# H09R9.net
KiCad netlist of a schematic drawn in EAGLE
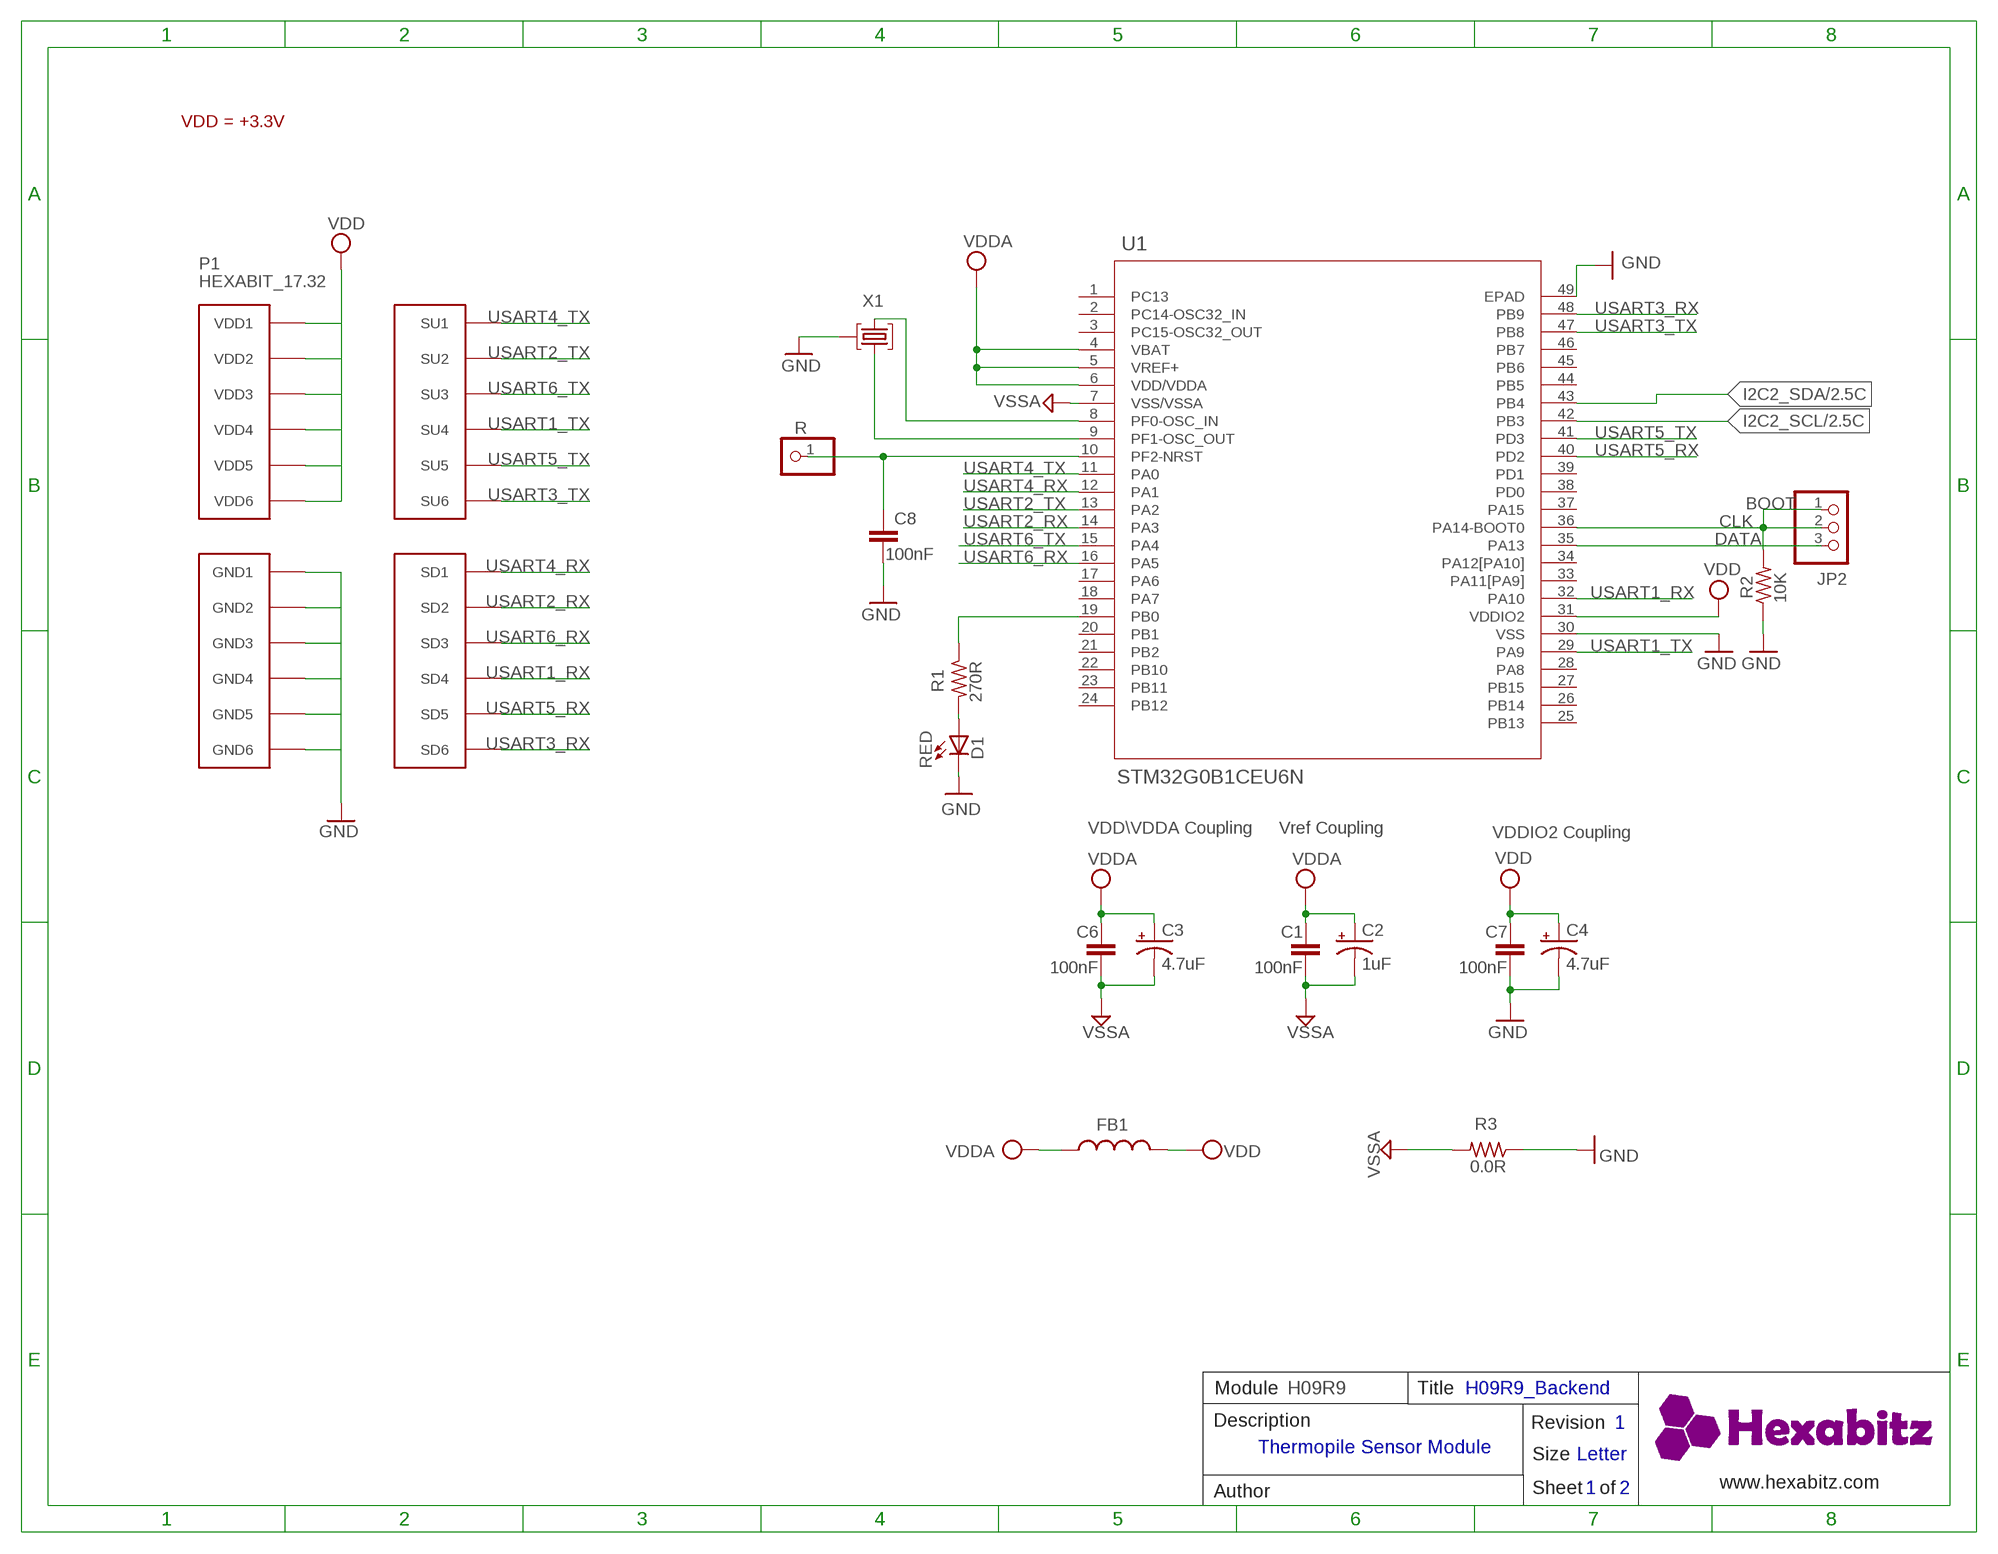
[diagram p0: schematic, sheet 1]
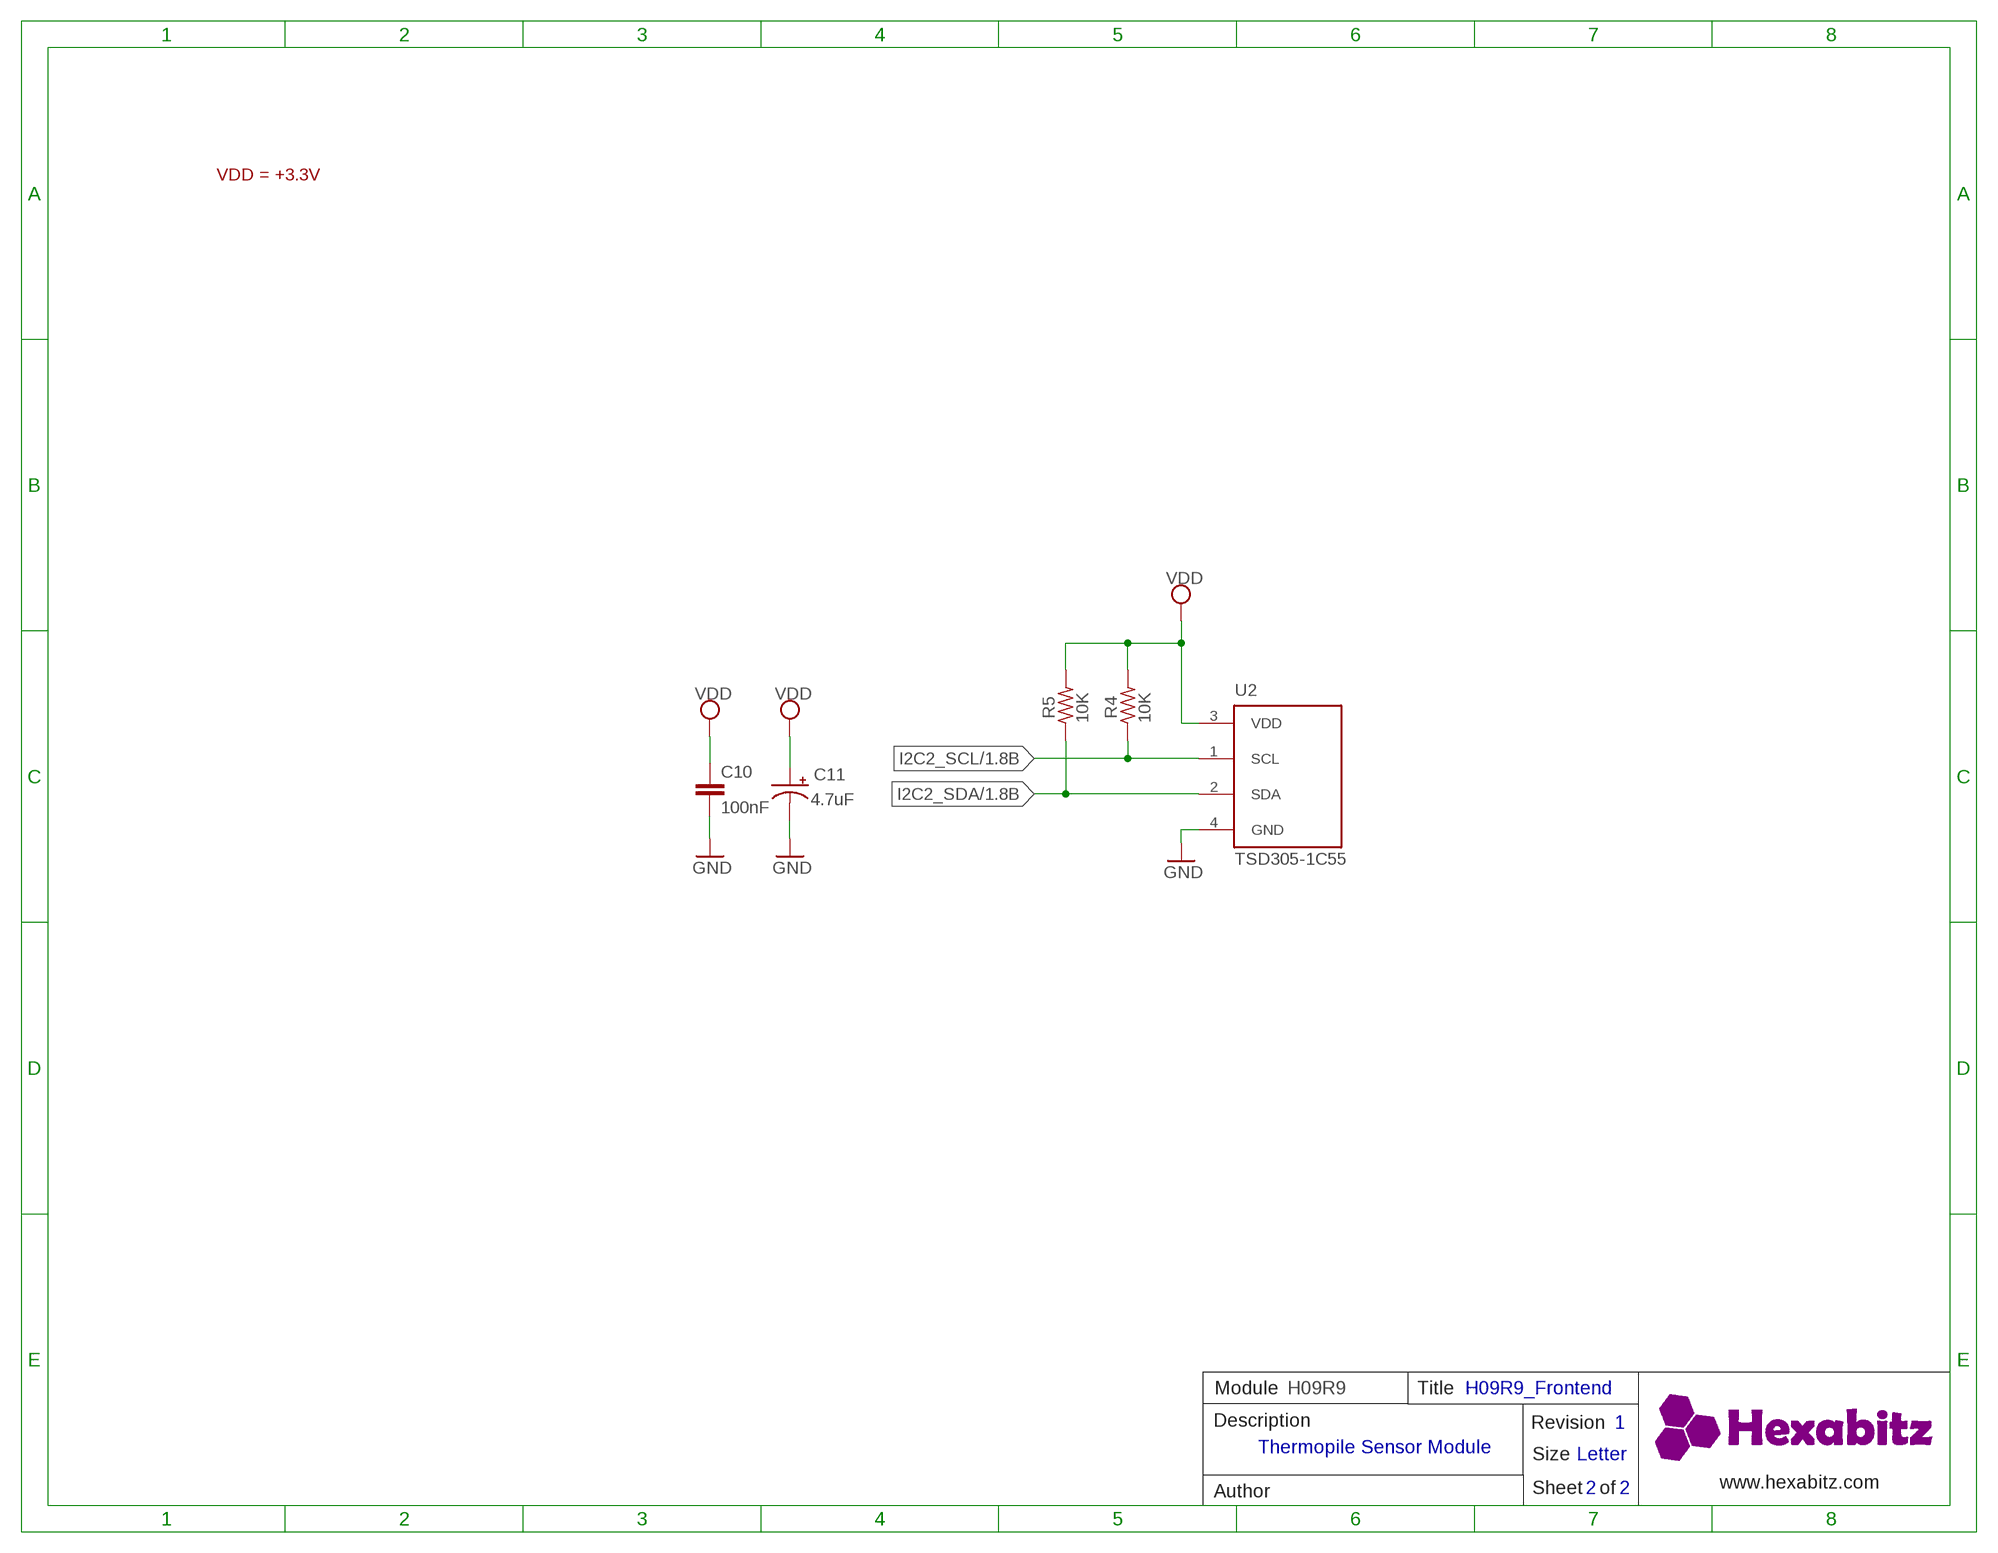
[diagram p1: schematic, sheet 2]

(export (version "E")
  (design (tool "Eeschema 10.0.6"))
  (components
    (comp (ref "C1")
      (value "100nF")
      (footprint "eagle-import:C-0603")
      (libsource (lib "eagle-import") (part "C-0603"))
    )
    (comp (ref "C2")
      (value "1uF")
      (footprint "eagle-import:C-0805-POL")
      (libsource (lib "eagle-import") (part "C-0805-POL"))
    )
    (comp (ref "C3")
      (value "4.7uF")
      (footprint "eagle-import:C-0805-POL")
      (libsource (lib "eagle-import") (part "C-0805-POL"))
    )
    (comp (ref "C4")
      (value "4.7uF")
      (footprint "eagle-import:C-0805-POL")
      (libsource (lib "eagle-import") (part "C-0805-POL"))
    )
    (comp (ref "C6")
      (value "100nF")
      (footprint "eagle-import:C-0603")
      (libsource (lib "eagle-import") (part "C-0603"))
    )
    (comp (ref "C7")
      (value "100nF")
      (footprint "eagle-import:C-0603")
      (libsource (lib "eagle-import") (part "C-0603"))
    )
    (comp (ref "C8")
      (value "100nF")
      (footprint "eagle-import:C-0603")
      (libsource (lib "eagle-import") (part "C-0603"))
    )
    (comp (ref "D1")
      (value "RED")
      (footprint "eagle-import:VLMS1300-GS08")
      (fields
        (field (name "MPN") "VLMS1300-GS08")
        (field (name "MFN") "Vishay")
        (field (name "MPN_1") "VLMS1300-GS08")
        (field (name "OCTOPART_URL") "https://octopart.com/vlms1300-gs08-vishay-21709201?r=sp&s=_gcP4_q8T1SC6PJQPTQ9yA")
      )
      (libsource (lib "eagle-import") (part "VLMS1300-GS08"))
    )
    (comp (ref "FB1")
      (value "FB-TDK_MMZ1608Y300B")
      (footprint "eagle-import:FB-TDK_MMZ1608Y300B")
      (fields
        (field (name "MFN") "TDK ")
        (field (name "MPN") "MMZ1608Y300B")
        (field (name "OCTOPART_URL") "https://octopart.com/mmz1608y300b-tdk-368280?r=sp&s=cd9_2ZEqQ9q9UNBuQgHAiA")
      )
      (libsource (lib "eagle-import") (part "FB-TDK_MMZ1608Y300B"))
    )
    (comp (ref "JP2")
      (value "PINHD-1X3")
      (footprint "eagle-import:1X03")
      (libsource (lib "eagle-import") (part "PINHD-1X3"))
    )
    (comp (ref "P1")
      (value "HEXABIT_17.32")
      (footprint "eagle-import:HEXABIT_17.32")
      (libsource (lib "eagle-import") (part "HEXABIT_?17.32"))
    )
    (comp (ref "R")
      (value "R")
      (footprint "eagle-import:1X01")
      (fields (field (name "MPN") "87227-1"))
      (libsource (lib "eagle-import") (part "PINHD-1X1"))
    )
    (comp (ref "R1")
      (value "270R")
      (footprint "eagle-import:R-0603")
      (libsource (lib "eagle-import") (part "R-0603"))
    )
    (comp (ref "R2")
      (value "10K")
      (footprint "eagle-import:R-0603")
      (libsource (lib "eagle-import") (part "R-0603"))
    )
    (comp (ref "R3")
      (value "0.0R")
      (footprint "eagle-import:R-0603")
      (fields
        (field (name "MFN") "Yageo")
        (field (name "MPN") "RC0603JR-070RL")
        (field (name "OCTOPART_URL") "https://octopart.com/rc0603jr-070rl-yageo-1241539?r=sp&s=X2NteqRjRNWrnx42Y0aliA")
        (field (name "RESISTANCE") "0.0 Ohm")
      )
      (libsource (lib "eagle-import") (part "R-0603"))
    )
    (comp (ref "U1")
      (value "STM32G0B1CEU6N")
      (footprint "eagle-import:HEXABITZ_ICS_QFN_B1CEU6_STM-L")
      (libsource (lib "eagle-import") (part "STM32G0B1CEU6N"))
    )
    (comp (ref "X1")
      (value "XTALL_CSTCE8M00G52")
      (footprint "eagle-import:XTALL_CSTCE8M00G52")
      (fields (field (name "MPN") "CSTCE8M00G52Z-R0"))
      (libsource (lib "eagle-import") (part "XTALL_CSTCE8M00G52"))
    )
    (comp (ref "C10")
      (value "100nF")
      (footprint "eagle-import:C-0603")
      (fields
        (field (name "CAPACITANCE") "100nF")
        (field (name "MFN") "AVX")
        (field (name "MPN") "0603YC104K4T2A")
        (field (name "OCTOPART_URL") "https://octopart.com/0603yc104k4t2a-avx+interconnect+%2F+elco-8120651")
        (field (name "TOLERANCE") "10%")
        (field (name "VOLTAGE_RATING") "16.0 V")
      )
      (libsource (lib "eagle-import") (part "C-0603"))
    )
    (comp (ref "C11")
      (value "4.7uF")
      (footprint "eagle-import:C-0805-POL")
      (fields
        (field (name "CAPACITANCE") "4.7uF")
        (field (name "MFN") "Panasonic")
        (field (name "MPN") "10TPU4R7MSI")
        (field (name "OCTOPART_URL") "https://octopart.com/10tpu4r7msi-panasonic-29487748")
        (field (name "TOLERANCE") "20%")
        (field (name "VOLTAGE_RATING") "10.0 V")
      )
      (libsource (lib "eagle-import") (part "C-0805-POL"))
    )
    (comp (ref "R4")
      (value "10K")
      (footprint "eagle-import:R-0603")
      (libsource (lib "eagle-import") (part "R-0603"))
    )
    (comp (ref "R5")
      (value "10K")
      (footprint "eagle-import:R-0603")
      (libsource (lib "eagle-import") (part "R-0603"))
    )
    (comp (ref "U2")
      (value "TSD305-1C55")
      (footprint "eagle-import:TEMPERATURESENSOR-TO5")
      (fields (field (name "MPN") "G-TPMO-101"))
      (libsource (lib "eagle-import") (part "TSD305-1C55"))
    )
  )
  (nets
    (net (code "1") (name "CLK") (class "Default")
      (node (ref "JP2") (pin "1") (pinfunction "1_1") (pintype "passive"))
      (node (ref "JP2") (pin "2") (pinfunction "2_2") (pintype "passive"))
      (node (ref "R2") (pin "2") (pinfunction "2_2") (pintype "passive"))
      (node (ref "U1") (pin "36") (pinfunction "PA14-BOOT0_36") (pintype "bidirectional"))
    )
    (net (code "2") (name "DATA") (class "Default")
      (node (ref "JP2") (pin "3") (pinfunction "3_3") (pintype "passive"))
      (node (ref "U1") (pin "35") (pinfunction "PA13_35") (pintype "bidirectional"))
    )
    (net (code "3") (name "GND") (class "Default")
      (node (ref "C10") (pin "2") (pinfunction "2_2") (pintype "passive"))
      (node (ref "C11") (pin "2") (pinfunction "-_2") (pintype "passive"))
      (node (ref "C4") (pin "2") (pinfunction "-_2") (pintype "passive"))
      (node (ref "C7") (pin "2") (pinfunction "2_2") (pintype "passive"))
      (node (ref "C8") (pin "2") (pinfunction "2_2") (pintype "passive"))
      (node (ref "D1") (pin "C") (pinfunction "C_C") (pintype "passive"))
      (node (ref "P1") (pin "PAD_PD10") (pinfunction "GND4_PAD_PD10") (pintype "power_in"))
      (node (ref "P1") (pin "PAD_PD11") (pinfunction "GND5_PAD_PD11") (pintype "power_in"))
      (node (ref "P1") (pin "PAD_PD12") (pinfunction "GND6_PAD_PD12") (pintype "power_in"))
      (node (ref "P1") (pin "PAD_PD7") (pinfunction "GND1_PAD_PD7") (pintype "power_in"))
      (node (ref "P1") (pin "PAD_PD8") (pinfunction "GND2_PAD_PD8") (pintype "power_in"))
      (node (ref "P1") (pin "PAD_PD9") (pinfunction "GND3_PAD_PD9") (pintype "power_in"))
      (node (ref "R2") (pin "1") (pinfunction "1_1") (pintype "passive"))
      (node (ref "R3") (pin "1") (pinfunction "1_1") (pintype "passive"))
      (node (ref "U1") (pin "30") (pinfunction "VSS_30") (pintype "passive"))
      (node (ref "U1") (pin "49") (pinfunction "EPAD_49") (pintype "passive"))
      (node (ref "U2") (pin "4") (pinfunction "GND_4") (pintype "power_in"))
      (node (ref "X1") (pin "P$2") (pinfunction "2_P$2") (pintype "passive"))
    )
    (net (code "4") (name "I2C2_SCL") (class "Default")
      (node (ref "R4") (pin "1") (pinfunction "1_1") (pintype "passive"))
      (node (ref "U1") (pin "42") (pinfunction "PB3_42") (pintype "bidirectional"))
      (node (ref "U2") (pin "1") (pinfunction "SCL_1") (pintype "bidirectional"))
    )
    (net (code "5") (name "I2C2_SDA") (class "Default")
      (node (ref "R5") (pin "1") (pinfunction "1_1") (pintype "passive"))
      (node (ref "U1") (pin "43") (pinfunction "PB4_43") (pintype "bidirectional"))
      (node (ref "U2") (pin "2") (pinfunction "SDA_2") (pintype "bidirectional"))
    )
    (net (code "6") (name "Net-(D1-PadA)") (class "Default")
      (node (ref "D1") (pin "A") (pinfunction "A_A") (pintype "passive"))
      (node (ref "R1") (pin "2") (pinfunction "2_2") (pintype "passive"))
    )
    (net (code "7") (name "Net-(U1-PB0)") (class "Default")
      (node (ref "R1") (pin "1") (pinfunction "1_1") (pintype "passive"))
      (node (ref "U1") (pin "19") (pinfunction "PB0_19") (pintype "bidirectional"))
    )
    (net (code "8") (name "Net-(U1-PF0-OSC_IN)") (class "Default")
      (node (ref "U1") (pin "8") (pinfunction "PF0-OSC_IN_8") (pintype "bidirectional"))
      (node (ref "X1") (pin "P$3") (pinfunction "3_P$3") (pintype "passive"))
    )
    (net (code "9") (name "Net-(U1-PF1-OSC_OUT)") (class "Default")
      (node (ref "U1") (pin "9") (pinfunction "PF1-OSC_OUT_9") (pintype "bidirectional"))
      (node (ref "X1") (pin "P$1") (pinfunction "1_P$1") (pintype "passive"))
    )
    (net (code "10") (name "Net-(U1-PF2-NRST)") (class "Default")
      (node (ref "C8") (pin "1") (pinfunction "1_1") (pintype "passive"))
      (node (ref "R") (pin "1") (pinfunction "1_1") (pintype "passive"))
      (node (ref "U1") (pin "10") (pinfunction "PF2-NRST_10") (pintype "bidirectional"))
    )
    (net (code "11") (name "USART1_RX") (class "Default")
      (node (ref "P1") (pin "PAD_PD4") (pinfunction "SD4_PAD_PD4") (pintype "bidirectional"))
      (node (ref "U1") (pin "32") (pinfunction "PA10_32") (pintype "bidirectional"))
    )
    (net (code "12") (name "USART1_TX") (class "Default")
      (node (ref "P1") (pin "PAD_PU4") (pinfunction "SU4_PAD_PU4") (pintype "bidirectional"))
      (node (ref "U1") (pin "29") (pinfunction "PA9_29") (pintype "bidirectional"))
    )
    (net (code "13") (name "USART2_RX") (class "Default")
      (node (ref "P1") (pin "PAD_PD2") (pinfunction "SD2_PAD_PD2") (pintype "bidirectional"))
      (node (ref "U1") (pin "14") (pinfunction "PA3_14") (pintype "bidirectional"))
    )
    (net (code "14") (name "USART2_TX") (class "Default")
      (node (ref "P1") (pin "PAD_PU2") (pinfunction "SU2_PAD_PU2") (pintype "bidirectional"))
      (node (ref "U1") (pin "13") (pinfunction "PA2_13") (pintype "bidirectional"))
    )
    (net (code "15") (name "USART3_RX") (class "Default")
      (node (ref "P1") (pin "PAD_PD6") (pinfunction "SD6_PAD_PD6") (pintype "bidirectional"))
      (node (ref "U1") (pin "48") (pinfunction "PB9_48") (pintype "bidirectional"))
    )
    (net (code "16") (name "USART3_TX") (class "Default")
      (node (ref "P1") (pin "PAD_PU6") (pinfunction "SU6_PAD_PU6") (pintype "bidirectional"))
      (node (ref "U1") (pin "47") (pinfunction "PB8_47") (pintype "bidirectional"))
    )
    (net (code "17") (name "USART4_RX") (class "Default")
      (node (ref "P1") (pin "PAD_PD1") (pinfunction "SD1_PAD_PD1") (pintype "bidirectional"))
      (node (ref "U1") (pin "12") (pinfunction "PA1_12") (pintype "bidirectional"))
    )
    (net (code "18") (name "USART4_TX") (class "Default")
      (node (ref "P1") (pin "PAD_PU1") (pinfunction "SU1_PAD_PU1") (pintype "bidirectional"))
      (node (ref "U1") (pin "11") (pinfunction "PA0_11") (pintype "bidirectional"))
    )
    (net (code "19") (name "USART5_RX") (class "Default")
      (node (ref "P1") (pin "PAD_PD5") (pinfunction "SD5_PAD_PD5") (pintype "bidirectional"))
      (node (ref "U1") (pin "40") (pinfunction "PD2_40") (pintype "bidirectional"))
    )
    (net (code "20") (name "USART5_TX") (class "Default")
      (node (ref "P1") (pin "PAD_PU5") (pinfunction "SU5_PAD_PU5") (pintype "bidirectional"))
      (node (ref "U1") (pin "41") (pinfunction "PD3_41") (pintype "bidirectional"))
    )
    (net (code "21") (name "USART6_RX") (class "Default")
      (node (ref "P1") (pin "PAD_PD3") (pinfunction "SD3_PAD_PD3") (pintype "bidirectional"))
      (node (ref "U1") (pin "16") (pinfunction "PA5_16") (pintype "bidirectional"))
    )
    (net (code "22") (name "USART6_TX") (class "Default")
      (node (ref "P1") (pin "PAD_PU3") (pinfunction "SU3_PAD_PU3") (pintype "bidirectional"))
      (node (ref "U1") (pin "15") (pinfunction "PA4_15") (pintype "bidirectional"))
    )
    (net (code "23") (name "VDD") (class "Default")
      (node (ref "C10") (pin "1") (pinfunction "1_1") (pintype "passive"))
      (node (ref "C11") (pin "1") (pinfunction "+_1") (pintype "passive"))
      (node (ref "C4") (pin "1") (pinfunction "+_1") (pintype "passive"))
      (node (ref "C7") (pin "1") (pinfunction "1_1") (pintype "passive"))
      (node (ref "FB1") (pin "2") (pinfunction "2_2") (pintype "passive"))
      (node (ref "P1") (pin "PAD_PU10") (pinfunction "VDD4_PAD_PU10") (pintype "power_in"))
      (node (ref "P1") (pin "PAD_PU11") (pinfunction "VDD5_PAD_PU11") (pintype "power_in"))
      (node (ref "P1") (pin "PAD_PU12") (pinfunction "VDD6_PAD_PU12") (pintype "power_in"))
      (node (ref "P1") (pin "PAD_PU7") (pinfunction "VDD1_PAD_PU7") (pintype "power_in"))
      (node (ref "P1") (pin "PAD_PU8") (pinfunction "VDD2_PAD_PU8") (pintype "power_in"))
      (node (ref "P1") (pin "PAD_PU9") (pinfunction "VDD3_PAD_PU9") (pintype "power_in"))
      (node (ref "R4") (pin "2") (pinfunction "2_2") (pintype "passive"))
      (node (ref "R5") (pin "2") (pinfunction "2_2") (pintype "passive"))
      (node (ref "U1") (pin "31") (pinfunction "VDDIO2_31") (pintype "power_in"))
      (node (ref "U2") (pin "3") (pinfunction "VDD_3") (pintype "power_in"))
    )
    (net (code "24") (name "VDDA") (class "Default")
      (node (ref "C1") (pin "1") (pinfunction "1_1") (pintype "passive"))
      (node (ref "C2") (pin "1") (pinfunction "+_1") (pintype "passive"))
      (node (ref "C3") (pin "1") (pinfunction "+_1") (pintype "passive"))
      (node (ref "C6") (pin "1") (pinfunction "1_1") (pintype "passive"))
      (node (ref "FB1") (pin "1") (pinfunction "1_1") (pintype "passive"))
      (node (ref "U1") (pin "4") (pinfunction "VBAT_4") (pintype "power_in"))
      (node (ref "U1") (pin "5") (pinfunction "VREF+_5") (pintype "power_in"))
      (node (ref "U1") (pin "6") (pinfunction "VDD/VDDA_6") (pintype "power_in"))
    )
    (net (code "25") (name "VSSA") (class "Default")
      (node (ref "C1") (pin "2") (pinfunction "2_2") (pintype "passive"))
      (node (ref "C2") (pin "2") (pinfunction "-_2") (pintype "passive"))
      (node (ref "C3") (pin "2") (pinfunction "-_2") (pintype "passive"))
      (node (ref "C6") (pin "2") (pinfunction "2_2") (pintype "passive"))
      (node (ref "R3") (pin "2") (pinfunction "2_2") (pintype "passive"))
      (node (ref "U1") (pin "7") (pinfunction "VSS/VSSA_7") (pintype "passive"))
    )
    (net (code "26") (name "unconnected-(U1-PA6-Pad17)") (class "Default")
      (node (ref "U1") (pin "17") (pinfunction "PA6_17") (pintype "bidirectional"))
    )
    (net (code "27") (name "unconnected-(U1-PA7-Pad18)") (class "Default")
      (node (ref "U1") (pin "18") (pinfunction "PA7_18") (pintype "bidirectional"))
    )
    (net (code "28") (name "unconnected-(U1-PA8-Pad28)") (class "Default")
      (node (ref "U1") (pin "28") (pinfunction "PA8_28") (pintype "bidirectional"))
    )
    (net (code "29") (name "unconnected-(U1-PA11[PA9]-Pad33)") (class "Default")
      (node (ref "U1") (pin "33") (pinfunction "PA11[PA9]_33") (pintype "bidirectional"))
    )
    (net (code "30") (name "unconnected-(U1-PA12[PA10]-Pad34)") (class "Default")
      (node (ref "U1") (pin "34") (pinfunction "PA12[PA10]_34") (pintype "bidirectional"))
    )
    (net (code "31") (name "unconnected-(U1-PA15-Pad37)") (class "Default")
      (node (ref "U1") (pin "37") (pinfunction "PA15_37") (pintype "bidirectional"))
    )
    (net (code "32") (name "unconnected-(U1-PB1-Pad20)") (class "Default")
      (node (ref "U1") (pin "20") (pinfunction "PB1_20") (pintype "bidirectional"))
    )
    (net (code "33") (name "unconnected-(U1-PB2-Pad21)") (class "Default")
      (node (ref "U1") (pin "21") (pinfunction "PB2_21") (pintype "bidirectional"))
    )
    (net (code "34") (name "unconnected-(U1-PB5-Pad44)") (class "Default")
      (node (ref "U1") (pin "44") (pinfunction "PB5_44") (pintype "bidirectional"))
    )
    (net (code "35") (name "unconnected-(U1-PB6-Pad45)") (class "Default")
      (node (ref "U1") (pin "45") (pinfunction "PB6_45") (pintype "bidirectional"))
    )
    (net (code "36") (name "unconnected-(U1-PB7-Pad46)") (class "Default")
      (node (ref "U1") (pin "46") (pinfunction "PB7_46") (pintype "bidirectional"))
    )
    (net (code "37") (name "unconnected-(U1-PB10-Pad22)") (class "Default")
      (node (ref "U1") (pin "22") (pinfunction "PB10_22") (pintype "bidirectional"))
    )
    (net (code "38") (name "unconnected-(U1-PB11-Pad23)") (class "Default")
      (node (ref "U1") (pin "23") (pinfunction "PB11_23") (pintype "bidirectional"))
    )
    (net (code "39") (name "unconnected-(U1-PB12-Pad24)") (class "Default")
      (node (ref "U1") (pin "24") (pinfunction "PB12_24") (pintype "bidirectional"))
    )
    (net (code "40") (name "unconnected-(U1-PB13-Pad25)") (class "Default")
      (node (ref "U1") (pin "25") (pinfunction "PB13_25") (pintype "bidirectional"))
    )
    (net (code "41") (name "unconnected-(U1-PB14-Pad26)") (class "Default")
      (node (ref "U1") (pin "26") (pinfunction "PB14_26") (pintype "bidirectional"))
    )
    (net (code "42") (name "unconnected-(U1-PB15-Pad27)") (class "Default")
      (node (ref "U1") (pin "27") (pinfunction "PB15_27") (pintype "bidirectional"))
    )
    (net (code "43") (name "unconnected-(U1-PC13-Pad1)") (class "Default")
      (node (ref "U1") (pin "1") (pinfunction "PC13_1") (pintype "bidirectional"))
    )
    (net (code "44") (name "unconnected-(U1-PC14-OSC32_IN-Pad2)") (class "Default")
      (node (ref "U1") (pin "2") (pinfunction "PC14-OSC32_IN_2") (pintype "bidirectional"))
    )
    (net (code "45") (name "unconnected-(U1-PC15-OSC32_OUT-Pad3)") (class "Default")
      (node (ref "U1") (pin "3") (pinfunction "PC15-OSC32_OUT_3") (pintype "bidirectional"))
    )
    (net (code "46") (name "unconnected-(U1-PD0-Pad38)") (class "Default")
      (node (ref "U1") (pin "38") (pinfunction "PD0_38") (pintype "bidirectional"))
    )
    (net (code "47") (name "unconnected-(U1-PD1-Pad39)") (class "Default")
      (node (ref "U1") (pin "39") (pinfunction "PD1_39") (pintype "bidirectional"))
    )
  )
)
